# lis3dh_v402.net
KiCad netlist of a schematic drawn in EAGLE
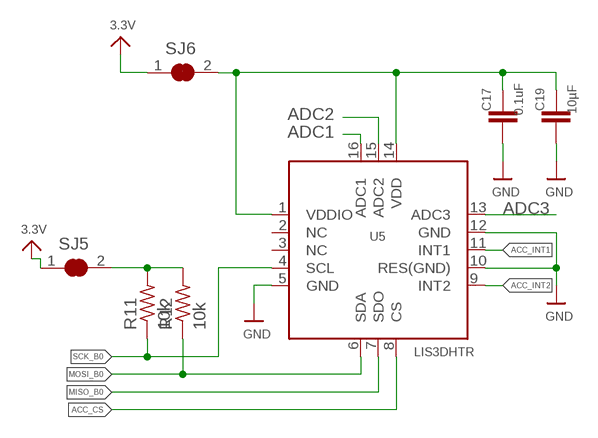
[diagram p0: schematic, sheet 1]

(export (version "E")
  (design (tool "Eeschema 10.0.6"))
  (components
    (comp (ref "C17")
      (value "0.1uF")
      (footprint "eagle-import:C0402")
      (libsource (lib "eagle-import") (part "C-EUC0402"))
    )
    (comp (ref "C19")
      (value "10µF")
      (footprint "eagle-import:C0402")
      (libsource (lib "eagle-import") (part "C-EUC0402"))
    )
    (comp (ref "R11")
      (value "10k")
      (footprint "eagle-import:R0402")
      (libsource (lib "eagle-import") (part "R-US_R0402"))
    )
    (comp (ref "R12")
      (value "10k")
      (footprint "eagle-import:R0402")
      (libsource (lib "eagle-import") (part "R-US_R0402"))
    )
    (comp (ref "SJ5")
      (value "SOLDERJUMPER_CLOSED")
      (footprint "eagle-import:SOLDERJUMPER_CLOSEDWIRE")
      (libsource (lib "eagle-import") (part "SOLDERJUMPER_CLOSED"))
    )
    (comp (ref "SJ6")
      (value "SOLDERJUMPER_CLOSED")
      (footprint "eagle-import:SOLDERJUMPER_CLOSEDWIRE")
      (libsource (lib "eagle-import") (part "SOLDERJUMPER_CLOSED"))
    )
    (comp (ref "U5")
      (value "LIS3DHTR")
      (footprint "eagle-import:LGA16_3X3MM")
      (libsource (lib "eagle-import") (part "ACCEL_LIS3DHTR"))
    )
  )
  (nets
    (net (code "1") (name "/ADC1") (class "Default")
      (node (ref "U5") (pin "16") (pinfunction "ADC1_16") (pintype "input"))
    )
    (net (code "2") (name "/ADC2") (class "Default")
      (node (ref "U5") (pin "15") (pinfunction "ADC2_15") (pintype "input"))
    )
    (net (code "3") (name "/ADC3") (class "Default")
      (node (ref "U5") (pin "13") (pinfunction "ADC3_13") (pintype "input"))
    )
    (net (code "4") (name "3.3V") (class "Default")
      (node (ref "SJ5") (pin "1") (pinfunction "1_1") (pintype "passive"))
      (node (ref "SJ6") (pin "1") (pinfunction "1_1") (pintype "passive"))
    )
    (net (code "5") (name "ACC_CS") (class "Default")
      (node (ref "U5") (pin "8") (pinfunction "CS_8") (pintype "input"))
    )
    (net (code "6") (name "ACC_INT1") (class "Default")
      (node (ref "U5") (pin "11") (pinfunction "INT1_11") (pintype "output"))
    )
    (net (code "7") (name "ACC_INT2") (class "Default")
      (node (ref "U5") (pin "9") (pinfunction "INT2_9") (pintype "output"))
    )
    (net (code "8") (name "GND") (class "Default")
      (node (ref "C17") (pin "2") (pinfunction "2_2") (pintype "passive"))
      (node (ref "C19") (pin "2") (pinfunction "2_2") (pintype "passive"))
      (node (ref "U5") (pin "10") (pinfunction "RES(GND)_10") (pintype "bidirectional"))
      (node (ref "U5") (pin "12") (pinfunction "GND_12") (pintype "power_in"))
      (node (ref "U5") (pin "5") (pinfunction "GND_5") (pintype "power_in"))
    )
    (net (code "9") (name "MISO_B0") (class "Default")
      (node (ref "U5") (pin "7") (pinfunction "SDO_7") (pintype "bidirectional"))
    )
    (net (code "10") (name "MOSI_B0") (class "Default")
      (node (ref "R12") (pin "1") (pinfunction "1_1") (pintype "passive"))
      (node (ref "U5") (pin "6") (pinfunction "SDA_6") (pintype "bidirectional"))
    )
    (net (code "11") (name "Net-(R11-Pad2)") (class "Default")
      (node (ref "R11") (pin "2") (pinfunction "2_2") (pintype "passive"))
      (node (ref "R12") (pin "2") (pinfunction "2_2") (pintype "passive"))
      (node (ref "SJ5") (pin "2") (pinfunction "2_2") (pintype "passive"))
    )
    (net (code "12") (name "Net-(U5-VDD)") (class "Default")
      (node (ref "C17") (pin "1") (pinfunction "1_1") (pintype "passive"))
      (node (ref "C19") (pin "1") (pinfunction "1_1") (pintype "passive"))
      (node (ref "SJ6") (pin "2") (pinfunction "2_2") (pintype "passive"))
      (node (ref "U5") (pin "1") (pinfunction "VDDIO_1") (pintype "power_in"))
      (node (ref "U5") (pin "14") (pinfunction "VDD_14") (pintype "power_in"))
    )
    (net (code "13") (name "SCK_B0") (class "Default")
      (node (ref "R11") (pin "1") (pinfunction "1_1") (pintype "passive"))
      (node (ref "U5") (pin "4") (pinfunction "SCL_4") (pintype "bidirectional"))
    )
    (net (code "14") (name "unconnected-(U5-NC-Pad2)") (class "Default")
      (node (ref "U5") (pin "2") (pinfunction "NC_2") (pintype "no_connect"))
    )
    (net (code "15") (name "unconnected-(U5-NC-Pad3)") (class "Default")
      (node (ref "U5") (pin "3") (pinfunction "NC_3") (pintype "no_connect"))
    )
  )
)
